# Power_USB.net
KiCad netlist of a schematic drawn in Altium Designer
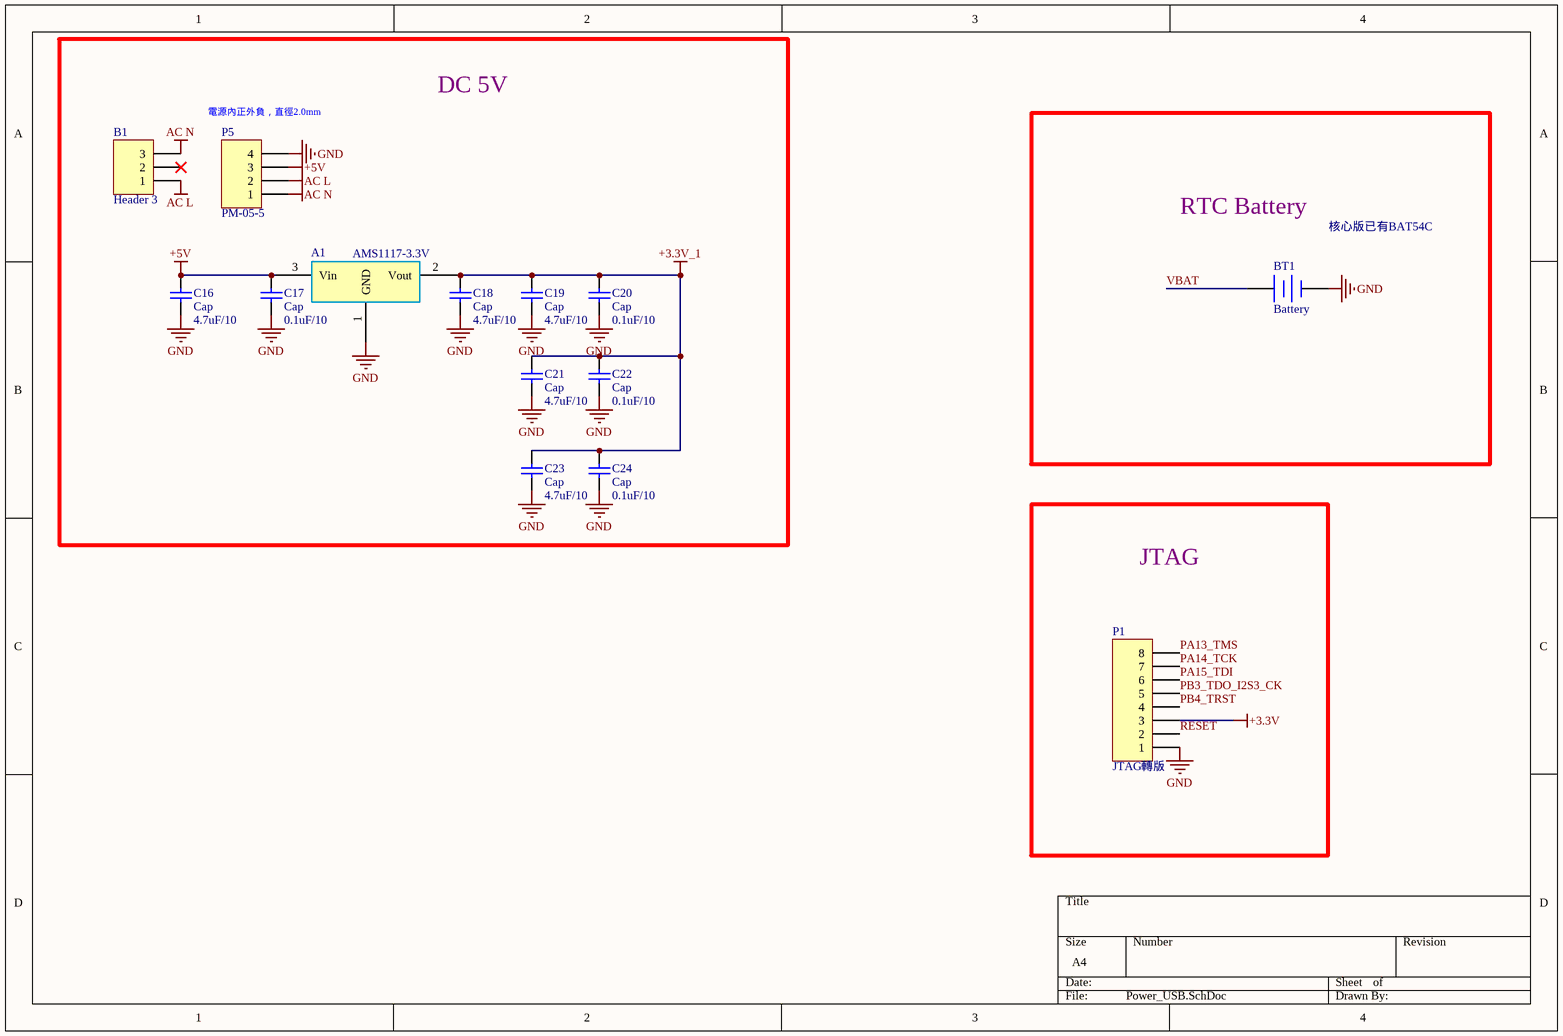
[diagram p0: Power_USB.SchDoc]

(export (version "E")
  (design (tool "Eeschema 10.0.6"))
  (components
    (comp (ref "A1")
      (value "AMS1117-3.3V")
      (footprint "AMS1117-3.3")
      (libsource (lib "lib-KJ") (part "AMS1117-3.3V"))
    )
    (comp (ref "B1")
      (value "Header 3")
      (footprint "歐式端子*3p")
      (description "Header, 3-Pin")
      (fields (field (name "PUBLISHER") "Altium Limited"))
      (libsource (lib "Miscellaneous Connectors") (part "Header 3"))
    )
    (comp (ref "BT1")
      (value "Battery")
      (footprint "CR1220 battery holder")
      (description "Multicell Battery")
      (fields (field (name "PUBLISHER") "Altium Limited"))
      (libsource (lib "Miscellaneous Devices") (part "Battery"))
    )
    (comp (ref "C16")
      (value "Cap")
      (footprint "0805")
      (description "Capacitor")
      (fields (field (name "ALTIUM_VALUE") "4.7uF/10") (field (name "PUBLISHER") "Altium Limited"))
      (libsource (lib "Miscellaneous Devices") (part "Cap"))
    )
    (comp (ref "C17")
      (value "Cap")
      (footprint "0805")
      (description "Capacitor")
      (fields (field (name "ALTIUM_VALUE") "0.1uF/10") (field (name "PUBLISHER") "Altium Limited"))
      (libsource (lib "Miscellaneous Devices") (part "Cap"))
    )
    (comp (ref "C18")
      (value "Cap")
      (footprint "0805")
      (description "Capacitor")
      (fields (field (name "ALTIUM_VALUE") "4.7uF/10") (field (name "PUBLISHER") "Altium Limited"))
      (libsource (lib "Miscellaneous Devices") (part "Cap"))
    )
    (comp (ref "C19")
      (value "Cap")
      (footprint "0805")
      (description "Capacitor")
      (fields (field (name "ALTIUM_VALUE") "4.7uF/10") (field (name "PUBLISHER") "Altium Limited"))
      (libsource (lib "Miscellaneous Devices") (part "Cap"))
    )
    (comp (ref "C20")
      (value "Cap")
      (footprint "0805")
      (description "Capacitor")
      (fields (field (name "ALTIUM_VALUE") "0.1uF/10") (field (name "PUBLISHER") "Altium Limited"))
      (libsource (lib "Miscellaneous Devices") (part "Cap"))
    )
    (comp (ref "C21")
      (value "Cap")
      (footprint "0805")
      (description "Capacitor")
      (fields (field (name "ALTIUM_VALUE") "4.7uF/10") (field (name "PUBLISHER") "Altium Limited"))
      (libsource (lib "Miscellaneous Devices") (part "Cap"))
    )
    (comp (ref "C22")
      (value "Cap")
      (footprint "0805")
      (description "Capacitor")
      (fields (field (name "ALTIUM_VALUE") "0.1uF/10") (field (name "PUBLISHER") "Altium Limited"))
      (libsource (lib "Miscellaneous Devices") (part "Cap"))
    )
    (comp (ref "C23")
      (value "Cap")
      (footprint "0805")
      (description "Capacitor")
      (fields (field (name "ALTIUM_VALUE") "4.7uF/10") (field (name "PUBLISHER") "Altium Limited"))
      (libsource (lib "Miscellaneous Devices") (part "Cap"))
    )
    (comp (ref "C24")
      (value "Cap")
      (footprint "0805")
      (description "Capacitor")
      (fields (field (name "ALTIUM_VALUE") "0.1uF/10") (field (name "PUBLISHER") "Altium Limited"))
      (libsource (lib "Miscellaneous Devices") (part "Cap"))
    )
    (comp (ref "P1")
      (value "JTAG轉版")
      (footprint "HDR1X8")
      (description "Header, 8-Pin")
      (fields (field (name "PUBLISHER") "Altium Limited"))
      (libsource (lib "Miscellaneous Connectors") (part "Header 8"))
    )
    (comp (ref "P5")
      (value "PM-05-5")
      (footprint "MW PM-05-5")
      (description "Header, 4-Pin")
      (fields (field (name "PUBLISHER") "Altium Limited"))
      (libsource (lib "Miscellaneous Connectors") (part "Header 4"))
    )
  )
  (nets
    (net (code "1") (name "+3.3V") (class "Default")
      (node (ref "P1") (pin "3") (pinfunction "3_3") (pintype "passive"))
    )
    (net (code "2") (name "+3.3V_1") (class "Default")
      (node (ref "A1") (pin "2") (pinfunction "Vout_2") (pintype "passive"))
      (node (ref "C18") (pin "1") (pinfunction "1_1") (pintype "passive"))
      (node (ref "C19") (pin "1") (pinfunction "1_1") (pintype "passive"))
      (node (ref "C20") (pin "1") (pinfunction "1_1") (pintype "passive"))
      (node (ref "C21") (pin "1") (pinfunction "1_1") (pintype "passive"))
      (node (ref "C22") (pin "1") (pinfunction "1_1") (pintype "passive"))
      (node (ref "C23") (pin "1") (pinfunction "1_1") (pintype "passive"))
      (node (ref "C24") (pin "1") (pinfunction "1_1") (pintype "passive"))
    )
    (net (code "3") (name "+5V") (class "Default")
      (node (ref "A1") (pin "3") (pinfunction "Vin_3") (pintype "passive"))
      (node (ref "C16") (pin "1") (pinfunction "1_1") (pintype "passive"))
      (node (ref "C17") (pin "1") (pinfunction "1_1") (pintype "passive"))
      (node (ref "P5") (pin "3") (pinfunction "3_3") (pintype "passive"))
    )
    (net (code "4") (name "/PA13_TMS") (class "Default")
      (node (ref "P1") (pin "8") (pinfunction "8_8") (pintype "passive"))
    )
    (net (code "5") (name "/PA14_TCK") (class "Default")
      (node (ref "P1") (pin "7") (pinfunction "7_7") (pintype "passive"))
    )
    (net (code "6") (name "/PA15_TDI") (class "Default")
      (node (ref "P1") (pin "6") (pinfunction "6_6") (pintype "passive"))
    )
    (net (code "7") (name "/PB3_TDO_I2S3_CK") (class "Default")
      (node (ref "P1") (pin "5") (pinfunction "5_5") (pintype "passive"))
    )
    (net (code "8") (name "/PB4_TRST") (class "Default")
      (node (ref "P1") (pin "4") (pinfunction "4_4") (pintype "passive"))
    )
    (net (code "9") (name "/RESET") (class "Default")
      (node (ref "P1") (pin "2") (pinfunction "2_2") (pintype "passive"))
    )
    (net (code "10") (name "/VBAT") (class "Default")
      (node (ref "BT1") (pin "1") (pinfunction "+_1") (pintype "passive"))
    )
    (net (code "11") (name "AC L") (class "Default")
      (node (ref "B1") (pin "1") (pinfunction "1_1") (pintype "passive"))
      (node (ref "P5") (pin "2") (pinfunction "2_2") (pintype "passive"))
    )
    (net (code "12") (name "AC N") (class "Default")
      (node (ref "B1") (pin "3") (pinfunction "3_3") (pintype "passive"))
      (node (ref "P5") (pin "1") (pinfunction "1_1") (pintype "passive"))
    )
    (net (code "13") (name "GND") (class "Default")
      (node (ref "A1") (pin "1") (pinfunction "GND_1") (pintype "passive"))
      (node (ref "BT1") (pin "2") (pinfunction "-_2") (pintype "passive"))
      (node (ref "C16") (pin "2") (pinfunction "2_2") (pintype "passive"))
      (node (ref "C17") (pin "2") (pinfunction "2_2") (pintype "passive"))
      (node (ref "C18") (pin "2") (pinfunction "2_2") (pintype "passive"))
      (node (ref "C19") (pin "2") (pinfunction "2_2") (pintype "passive"))
      (node (ref "C20") (pin "2") (pinfunction "2_2") (pintype "passive"))
      (node (ref "C21") (pin "2") (pinfunction "2_2") (pintype "passive"))
      (node (ref "C22") (pin "2") (pinfunction "2_2") (pintype "passive"))
      (node (ref "C23") (pin "2") (pinfunction "2_2") (pintype "passive"))
      (node (ref "C24") (pin "2") (pinfunction "2_2") (pintype "passive"))
      (node (ref "P1") (pin "1") (pinfunction "1_1") (pintype "passive"))
      (node (ref "P5") (pin "4") (pinfunction "4_4") (pintype "passive"))
    )
    (net (code "14") (name "unconnected-(B1-Pad2)") (class "Default")
      (node (ref "B1") (pin "2") (pinfunction "2_2") (pintype "passive+no_connect"))
    )
  )
)
